# working.net
KiCad netlist of a schematic drawn in EAGLE
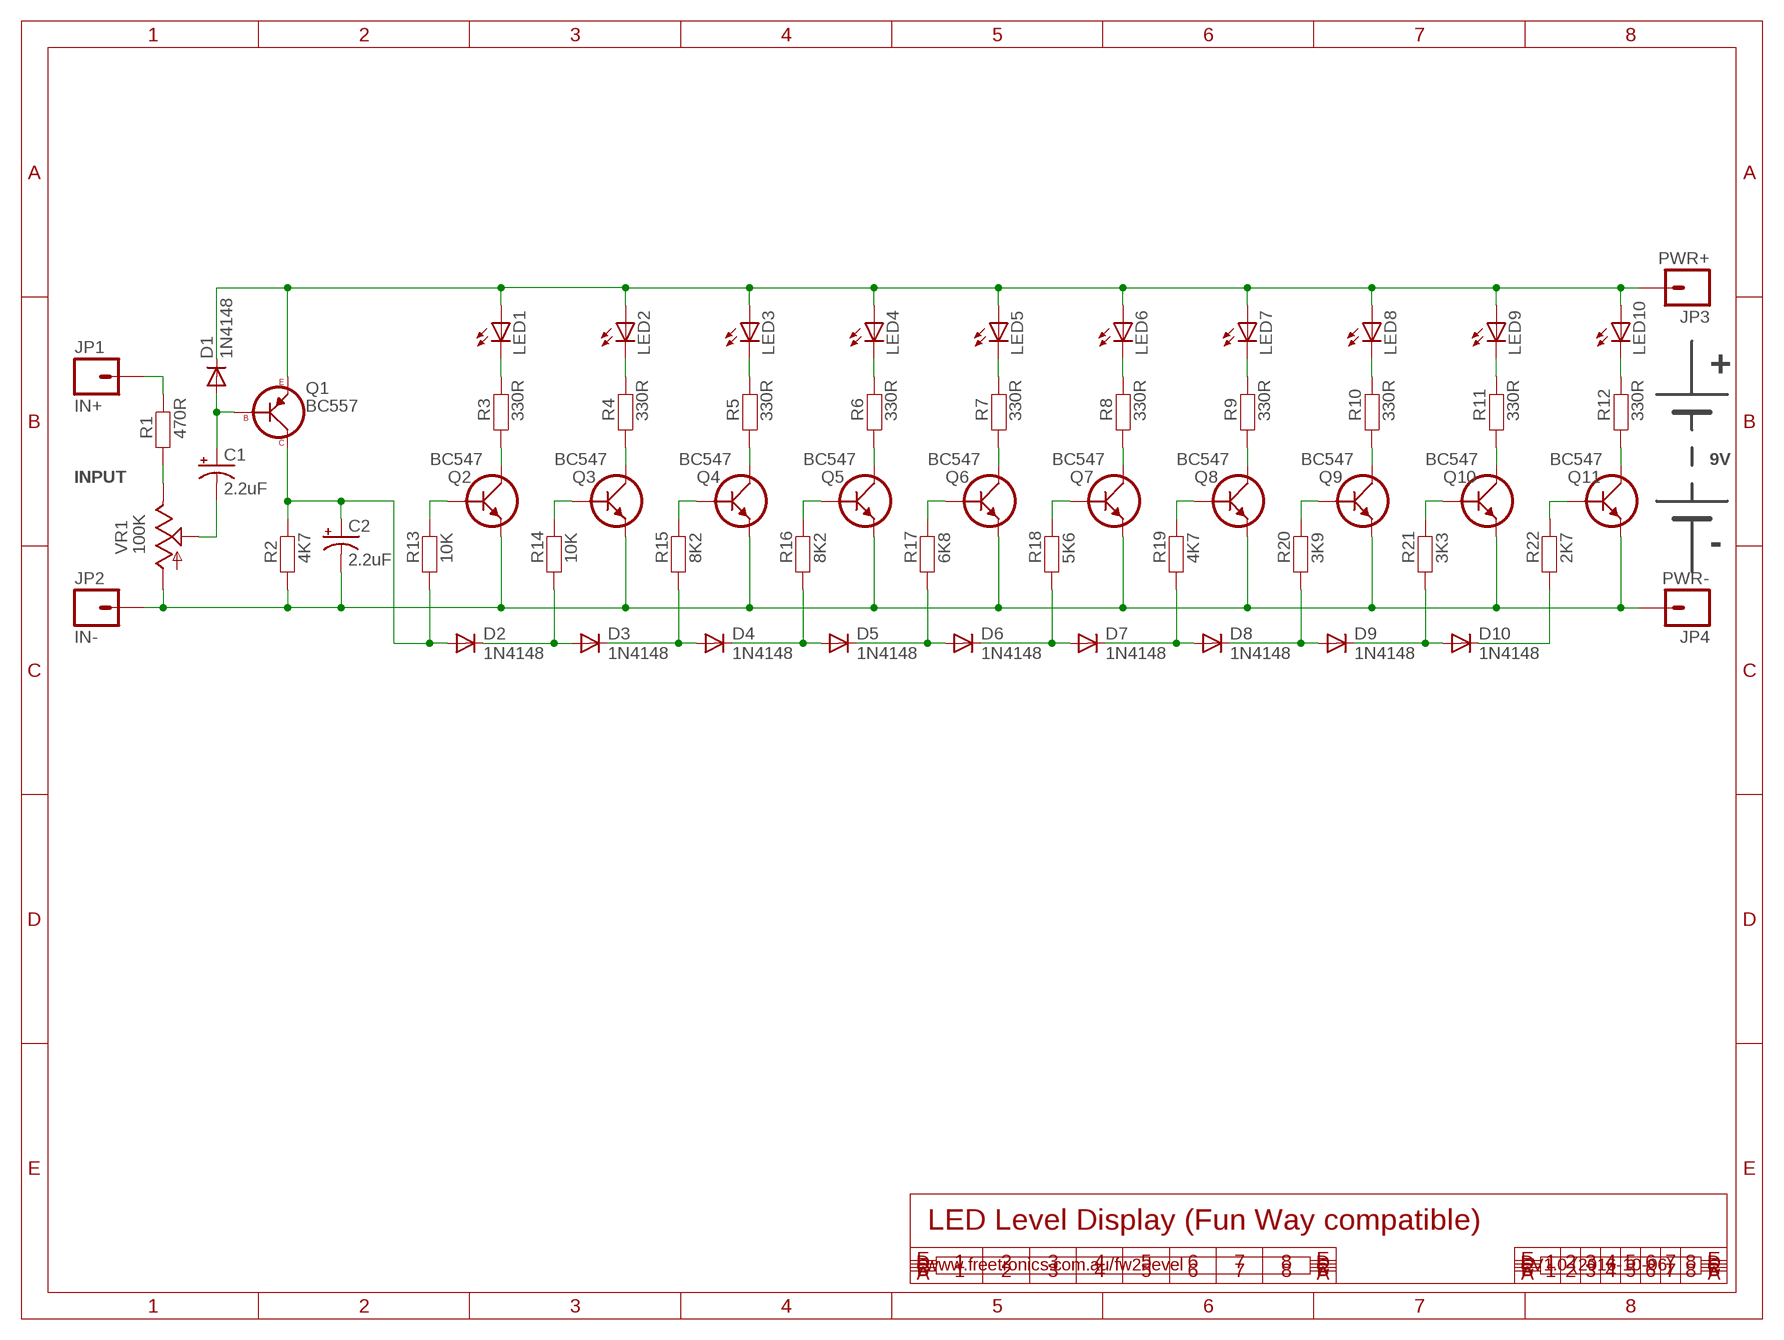
[diagram p0: schematic, sheet 1]

(export (version "E")
  (design (tool "Eeschema 10.0.6"))
  (components
    (comp (ref "C1")
      (value "2.2uF")
      (footprint "eagle-import:CPOL-RADIAL-100UF-25V")
      (libsource (lib "eagle-import") (part "CAP_POLPTH1"))
    )
    (comp (ref "C2")
      (value "2.2uF")
      (footprint "eagle-import:CPOL-RADIAL-100UF-25V")
      (libsource (lib "eagle-import") (part "CAP_POLPTH1"))
    )
    (comp (ref "D1")
      (value "1N4148")
      (footprint "eagle-import:DIODE-1N914L")
      (libsource (lib "eagle-import") (part "DIODE1N914L"))
    )
    (comp (ref "D2")
      (value "1N4148")
      (footprint "eagle-import:DIODE-1N914L")
      (libsource (lib "eagle-import") (part "DIODE1N914L"))
    )
    (comp (ref "D3")
      (value "1N4148")
      (footprint "eagle-import:DIODE-1N914L")
      (libsource (lib "eagle-import") (part "DIODE1N914L"))
    )
    (comp (ref "D4")
      (value "1N4148")
      (footprint "eagle-import:DIODE-1N914L")
      (libsource (lib "eagle-import") (part "DIODE1N914L"))
    )
    (comp (ref "D5")
      (value "1N4148")
      (footprint "eagle-import:DIODE-1N914L")
      (libsource (lib "eagle-import") (part "DIODE1N914L"))
    )
    (comp (ref "D6")
      (value "1N4148")
      (footprint "eagle-import:DIODE-1N914L")
      (libsource (lib "eagle-import") (part "DIODE1N914L"))
    )
    (comp (ref "D7")
      (value "1N4148")
      (footprint "eagle-import:DIODE-1N914L")
      (libsource (lib "eagle-import") (part "DIODE1N914L"))
    )
    (comp (ref "D8")
      (value "1N4148")
      (footprint "eagle-import:DIODE-1N914L")
      (libsource (lib "eagle-import") (part "DIODE1N914L"))
    )
    (comp (ref "D9")
      (value "1N4148")
      (footprint "eagle-import:DIODE-1N914L")
      (libsource (lib "eagle-import") (part "DIODE1N914L"))
    )
    (comp (ref "D10")
      (value "1N4148")
      (footprint "eagle-import:DIODE-1N914L")
      (libsource (lib "eagle-import") (part "DIODE1N914L"))
    )
    (comp (ref "JP1")
      (value "IN+")
      (footprint "eagle-import:1X01")
      (libsource (lib "eagle-import") (part "M01PTH"))
    )
    (comp (ref "JP2")
      (value "IN-")
      (footprint "eagle-import:1X01")
      (libsource (lib "eagle-import") (part "M01PTH"))
    )
    (comp (ref "JP3")
      (value "PWR+")
      (footprint "eagle-import:1X01")
      (libsource (lib "eagle-import") (part "M01PTH"))
    )
    (comp (ref "JP4")
      (value "PWR-")
      (footprint "eagle-import:1X01")
      (libsource (lib "eagle-import") (part "M01PTH"))
    )
    (comp (ref "LED1")
      (value "LED5MML")
      (footprint "eagle-import:LED5MMLARGE")
      (libsource (lib "eagle-import") (part "LED5MML"))
    )
    (comp (ref "LED2")
      (value "LED5MML")
      (footprint "eagle-import:LED5MMLARGE")
      (libsource (lib "eagle-import") (part "LED5MML"))
    )
    (comp (ref "LED3")
      (value "LED5MML")
      (footprint "eagle-import:LED5MMLARGE")
      (libsource (lib "eagle-import") (part "LED5MML"))
    )
    (comp (ref "LED4")
      (value "LED5MML")
      (footprint "eagle-import:LED5MMLARGE")
      (libsource (lib "eagle-import") (part "LED5MML"))
    )
    (comp (ref "LED5")
      (value "LED5MML")
      (footprint "eagle-import:LED5MMLARGE")
      (libsource (lib "eagle-import") (part "LED5MML"))
    )
    (comp (ref "LED6")
      (value "LED5MML")
      (footprint "eagle-import:LED5MMLARGE")
      (libsource (lib "eagle-import") (part "LED5MML"))
    )
    (comp (ref "LED7")
      (value "LED5MML")
      (footprint "eagle-import:LED5MMLARGE")
      (libsource (lib "eagle-import") (part "LED5MML"))
    )
    (comp (ref "LED8")
      (value "LED5MML")
      (footprint "eagle-import:LED5MMLARGE")
      (libsource (lib "eagle-import") (part "LED5MML"))
    )
    (comp (ref "LED9")
      (value "LED5MML")
      (footprint "eagle-import:LED5MMLARGE")
      (libsource (lib "eagle-import") (part "LED5MML"))
    )
    (comp (ref "LED10")
      (value "LED5MML")
      (footprint "eagle-import:LED5MMLARGE")
      (libsource (lib "eagle-import") (part "LED5MML"))
    )
    (comp (ref "Q1")
      (value "BC557")
      (footprint "eagle-import:TO-92")
      (libsource (lib "eagle-import") (part "BC557"))
    )
    (comp (ref "Q2")
      (value "BC547")
      (footprint "eagle-import:TO-92")
      (libsource (lib "eagle-import") (part "BC547"))
    )
    (comp (ref "Q3")
      (value "BC547")
      (footprint "eagle-import:TO-92")
      (libsource (lib "eagle-import") (part "BC547"))
    )
    (comp (ref "Q4")
      (value "BC547")
      (footprint "eagle-import:TO-92")
      (libsource (lib "eagle-import") (part "BC547"))
    )
    (comp (ref "Q5")
      (value "BC547")
      (footprint "eagle-import:TO-92")
      (libsource (lib "eagle-import") (part "BC547"))
    )
    (comp (ref "Q6")
      (value "BC547")
      (footprint "eagle-import:TO-92")
      (libsource (lib "eagle-import") (part "BC547"))
    )
    (comp (ref "Q7")
      (value "BC547")
      (footprint "eagle-import:TO-92")
      (libsource (lib "eagle-import") (part "BC547"))
    )
    (comp (ref "Q8")
      (value "BC547")
      (footprint "eagle-import:TO-92")
      (libsource (lib "eagle-import") (part "BC547"))
    )
    (comp (ref "Q9")
      (value "BC547")
      (footprint "eagle-import:TO-92")
      (libsource (lib "eagle-import") (part "BC547"))
    )
    (comp (ref "Q10")
      (value "BC547")
      (footprint "eagle-import:TO-92")
      (libsource (lib "eagle-import") (part "BC547"))
    )
    (comp (ref "Q11")
      (value "BC547")
      (footprint "eagle-import:TO-92")
      (libsource (lib "eagle-import") (part "BC547"))
    )
    (comp (ref "R1")
      (value "470R")
      (footprint "eagle-import:AXIAL-0.4-LARGE")
      (libsource (lib "eagle-import") (part "FREETRONICS_RESISTORPTH3"))
    )
    (comp (ref "R2")
      (value "4K7")
      (footprint "eagle-import:AXIAL-0.4-LARGE")
      (libsource (lib "eagle-import") (part "FREETRONICS_RESISTORPTH3"))
    )
    (comp (ref "R3")
      (value "330R")
      (footprint "eagle-import:0309VW")
      (libsource (lib "eagle-import") (part "RESISTORVERT3"))
    )
    (comp (ref "R4")
      (value "330R")
      (footprint "eagle-import:0309VW")
      (libsource (lib "eagle-import") (part "RESISTORVERT3"))
    )
    (comp (ref "R5")
      (value "330R")
      (footprint "eagle-import:0309VW")
      (libsource (lib "eagle-import") (part "RESISTORVERT3"))
    )
    (comp (ref "R6")
      (value "330R")
      (footprint "eagle-import:0309VW")
      (libsource (lib "eagle-import") (part "RESISTORVERT3"))
    )
    (comp (ref "R7")
      (value "330R")
      (footprint "eagle-import:0309VW")
      (libsource (lib "eagle-import") (part "RESISTORVERT3"))
    )
    (comp (ref "R8")
      (value "330R")
      (footprint "eagle-import:0309VW")
      (libsource (lib "eagle-import") (part "RESISTORVERT3"))
    )
    (comp (ref "R9")
      (value "330R")
      (footprint "eagle-import:0309VW")
      (libsource (lib "eagle-import") (part "RESISTORVERT3"))
    )
    (comp (ref "R10")
      (value "330R")
      (footprint "eagle-import:0309VW")
      (libsource (lib "eagle-import") (part "RESISTORVERT3"))
    )
    (comp (ref "R11")
      (value "330R")
      (footprint "eagle-import:0309VW")
      (libsource (lib "eagle-import") (part "RESISTORVERT3"))
    )
    (comp (ref "R12")
      (value "330R")
      (footprint "eagle-import:0309VW")
      (libsource (lib "eagle-import") (part "RESISTORVERT3"))
    )
    (comp (ref "R13")
      (value "10K")
      (footprint "eagle-import:0309VW")
      (libsource (lib "eagle-import") (part "RESISTORVERT3"))
    )
    (comp (ref "R14")
      (value "10K")
      (footprint "eagle-import:0309VW")
      (libsource (lib "eagle-import") (part "RESISTORVERT3"))
    )
    (comp (ref "R15")
      (value "8K2")
      (footprint "eagle-import:0309VW")
      (libsource (lib "eagle-import") (part "RESISTORVERT3"))
    )
    (comp (ref "R16")
      (value "8K2")
      (footprint "eagle-import:0309VW")
      (libsource (lib "eagle-import") (part "RESISTORVERT3"))
    )
    (comp (ref "R17")
      (value "6K8")
      (footprint "eagle-import:0309VW")
      (libsource (lib "eagle-import") (part "RESISTORVERT3"))
    )
    (comp (ref "R18")
      (value "5K6")
      (footprint "eagle-import:0309VW")
      (libsource (lib "eagle-import") (part "RESISTORVERT3"))
    )
    (comp (ref "R19")
      (value "4K7")
      (footprint "eagle-import:0309VW")
      (libsource (lib "eagle-import") (part "RESISTORVERT3"))
    )
    (comp (ref "R20")
      (value "3K9")
      (footprint "eagle-import:0309VW")
      (libsource (lib "eagle-import") (part "RESISTORVERT3"))
    )
    (comp (ref "R21")
      (value "3K3")
      (footprint "eagle-import:0309VW")
      (libsource (lib "eagle-import") (part "RESISTORVERT3"))
    )
    (comp (ref "R22")
      (value "2K7")
      (footprint "eagle-import:0309VW")
      (libsource (lib "eagle-import") (part "RESISTORVERT3"))
    )
    (comp (ref "VR1")
      (value "100K")
      (footprint "eagle-import:6MM")
      (libsource (lib "eagle-import") (part "TRIM"))
    )
  )
  (nets
    (net (code "1") (name "Net-(C1-+)") (class "Default")
      (node (ref "C1") (pin "1") (pinfunction "+_1") (pintype "passive"))
      (node (ref "D1") (pin "A") (pinfunction "A_A") (pintype "passive"))
      (node (ref "Q1") (pin "2") (pinfunction "B_2") (pintype "passive"))
    )
    (net (code "2") (name "Net-(C1--)") (class "Default")
      (node (ref "C1") (pin "2") (pinfunction "-_2") (pintype "passive"))
      (node (ref "VR1") (pin "S") (pinfunction "S_S") (pintype "passive"))
    )
    (net (code "3") (name "Net-(C2-+)") (class "Default")
      (node (ref "C2") (pin "1") (pinfunction "+_1") (pintype "passive"))
      (node (ref "D2") (pin "A") (pinfunction "A_A") (pintype "passive"))
      (node (ref "Q1") (pin "1") (pinfunction "C_1") (pintype "passive"))
      (node (ref "R13") (pin "1") (pinfunction "1_1") (pintype "passive"))
      (node (ref "R2") (pin "P$2") (pinfunction "2_P$2") (pintype "passive"))
    )
    (net (code "4") (name "Net-(C2--)") (class "Default")
      (node (ref "C2") (pin "2") (pinfunction "-_2") (pintype "passive"))
      (node (ref "JP2") (pin "1") (pinfunction "1_1") (pintype "passive"))
      (node (ref "JP4") (pin "1") (pinfunction "1_1") (pintype "passive"))
      (node (ref "Q10") (pin "3") (pinfunction "E_3") (pintype "passive"))
      (node (ref "Q11") (pin "3") (pinfunction "E_3") (pintype "passive"))
      (node (ref "Q2") (pin "3") (pinfunction "E_3") (pintype "passive"))
      (node (ref "Q3") (pin "3") (pinfunction "E_3") (pintype "passive"))
      (node (ref "Q4") (pin "3") (pinfunction "E_3") (pintype "passive"))
      (node (ref "Q5") (pin "3") (pinfunction "E_3") (pintype "passive"))
      (node (ref "Q6") (pin "3") (pinfunction "E_3") (pintype "passive"))
      (node (ref "Q7") (pin "3") (pinfunction "E_3") (pintype "passive"))
      (node (ref "Q8") (pin "3") (pinfunction "E_3") (pintype "passive"))
      (node (ref "Q9") (pin "3") (pinfunction "E_3") (pintype "passive"))
      (node (ref "R2") (pin "P$1") (pinfunction "1_P$1") (pintype "passive"))
      (node (ref "VR1") (pin "A") (pinfunction "A_A") (pintype "passive"))
    )
    (net (code "5") (name "Net-(D2-PadC)") (class "Default")
      (node (ref "D2") (pin "C") (pinfunction "C_C") (pintype "passive"))
      (node (ref "D3") (pin "A") (pinfunction "A_A") (pintype "passive"))
      (node (ref "R14") (pin "1") (pinfunction "1_1") (pintype "passive"))
    )
    (net (code "6") (name "Net-(D3-PadC)") (class "Default")
      (node (ref "D3") (pin "C") (pinfunction "C_C") (pintype "passive"))
      (node (ref "D4") (pin "A") (pinfunction "A_A") (pintype "passive"))
      (node (ref "R15") (pin "1") (pinfunction "1_1") (pintype "passive"))
    )
    (net (code "7") (name "Net-(D4-PadC)") (class "Default")
      (node (ref "D4") (pin "C") (pinfunction "C_C") (pintype "passive"))
      (node (ref "D5") (pin "A") (pinfunction "A_A") (pintype "passive"))
      (node (ref "R16") (pin "1") (pinfunction "1_1") (pintype "passive"))
    )
    (net (code "8") (name "Net-(D5-PadC)") (class "Default")
      (node (ref "D5") (pin "C") (pinfunction "C_C") (pintype "passive"))
      (node (ref "D6") (pin "A") (pinfunction "A_A") (pintype "passive"))
      (node (ref "R17") (pin "1") (pinfunction "1_1") (pintype "passive"))
    )
    (net (code "9") (name "Net-(D6-PadC)") (class "Default")
      (node (ref "D6") (pin "C") (pinfunction "C_C") (pintype "passive"))
      (node (ref "D7") (pin "A") (pinfunction "A_A") (pintype "passive"))
      (node (ref "R18") (pin "1") (pinfunction "1_1") (pintype "passive"))
    )
    (net (code "10") (name "Net-(D7-PadC)") (class "Default")
      (node (ref "D7") (pin "C") (pinfunction "C_C") (pintype "passive"))
      (node (ref "D8") (pin "A") (pinfunction "A_A") (pintype "passive"))
      (node (ref "R19") (pin "1") (pinfunction "1_1") (pintype "passive"))
    )
    (net (code "11") (name "Net-(D8-PadC)") (class "Default")
      (node (ref "D8") (pin "C") (pinfunction "C_C") (pintype "passive"))
      (node (ref "D9") (pin "A") (pinfunction "A_A") (pintype "passive"))
      (node (ref "R20") (pin "1") (pinfunction "1_1") (pintype "passive"))
    )
    (net (code "12") (name "Net-(D10-PadA)") (class "Default")
      (node (ref "D10") (pin "A") (pinfunction "A_A") (pintype "passive"))
      (node (ref "D9") (pin "C") (pinfunction "C_C") (pintype "passive"))
      (node (ref "R21") (pin "1") (pinfunction "1_1") (pintype "passive"))
    )
    (net (code "13") (name "Net-(D10-PadC)") (class "Default")
      (node (ref "D10") (pin "C") (pinfunction "C_C") (pintype "passive"))
      (node (ref "R22") (pin "1") (pinfunction "1_1") (pintype "passive"))
    )
    (net (code "14") (name "Net-(LED1-C)") (class "Default")
      (node (ref "LED1") (pin "K") (pinfunction "C_K") (pintype "passive"))
      (node (ref "R3") (pin "1") (pinfunction "1_1") (pintype "passive"))
    )
    (net (code "15") (name "Net-(LED2-C)") (class "Default")
      (node (ref "LED2") (pin "K") (pinfunction "C_K") (pintype "passive"))
      (node (ref "R4") (pin "1") (pinfunction "1_1") (pintype "passive"))
    )
    (net (code "16") (name "Net-(LED3-C)") (class "Default")
      (node (ref "LED3") (pin "K") (pinfunction "C_K") (pintype "passive"))
      (node (ref "R5") (pin "1") (pinfunction "1_1") (pintype "passive"))
    )
    (net (code "17") (name "Net-(LED4-C)") (class "Default")
      (node (ref "LED4") (pin "K") (pinfunction "C_K") (pintype "passive"))
      (node (ref "R6") (pin "1") (pinfunction "1_1") (pintype "passive"))
    )
    (net (code "18") (name "Net-(LED5-C)") (class "Default")
      (node (ref "LED5") (pin "K") (pinfunction "C_K") (pintype "passive"))
      (node (ref "R7") (pin "1") (pinfunction "1_1") (pintype "passive"))
    )
    (net (code "19") (name "Net-(LED6-C)") (class "Default")
      (node (ref "LED6") (pin "K") (pinfunction "C_K") (pintype "passive"))
      (node (ref "R8") (pin "1") (pinfunction "1_1") (pintype "passive"))
    )
    (net (code "20") (name "Net-(LED7-C)") (class "Default")
      (node (ref "LED7") (pin "K") (pinfunction "C_K") (pintype "passive"))
      (node (ref "R9") (pin "1") (pinfunction "1_1") (pintype "passive"))
    )
    (net (code "21") (name "Net-(LED8-C)") (class "Default")
      (node (ref "LED8") (pin "K") (pinfunction "C_K") (pintype "passive"))
      (node (ref "R10") (pin "1") (pinfunction "1_1") (pintype "passive"))
    )
    (net (code "22") (name "Net-(LED9-C)") (class "Default")
      (node (ref "LED9") (pin "K") (pinfunction "C_K") (pintype "passive"))
      (node (ref "R11") (pin "1") (pinfunction "1_1") (pintype "passive"))
    )
    (net (code "23") (name "Net-(LED10-C)") (class "Default")
      (node (ref "LED10") (pin "K") (pinfunction "C_K") (pintype "passive"))
      (node (ref "R12") (pin "1") (pinfunction "1_1") (pintype "passive"))
    )
    (net (code "24") (name "Net-(Q1-E)") (class "Default")
      (node (ref "D1") (pin "C") (pinfunction "C_C") (pintype "passive"))
      (node (ref "JP3") (pin "1") (pinfunction "1_1") (pintype "passive"))
      (node (ref "LED1") (pin "A") (pinfunction "A_A") (pintype "passive"))
      (node (ref "LED10") (pin "A") (pinfunction "A_A") (pintype "passive"))
      (node (ref "LED2") (pin "A") (pinfunction "A_A") (pintype "passive"))
      (node (ref "LED3") (pin "A") (pinfunction "A_A") (pintype "passive"))
      (node (ref "LED4") (pin "A") (pinfunction "A_A") (pintype "passive"))
      (node (ref "LED5") (pin "A") (pinfunction "A_A") (pintype "passive"))
      (node (ref "LED6") (pin "A") (pinfunction "A_A") (pintype "passive"))
      (node (ref "LED7") (pin "A") (pinfunction "A_A") (pintype "passive"))
      (node (ref "LED8") (pin "A") (pinfunction "A_A") (pintype "passive"))
      (node (ref "LED9") (pin "A") (pinfunction "A_A") (pintype "passive"))
      (node (ref "Q1") (pin "3") (pinfunction "E_3") (pintype "passive"))
    )
    (net (code "25") (name "Net-(Q2-B)") (class "Default")
      (node (ref "Q2") (pin "2") (pinfunction "B_2") (pintype "passive"))
      (node (ref "R13") (pin "2") (pinfunction "2_2") (pintype "passive"))
    )
    (net (code "26") (name "Net-(Q2-C)") (class "Default")
      (node (ref "Q2") (pin "1") (pinfunction "C_1") (pintype "passive"))
      (node (ref "R3") (pin "2") (pinfunction "2_2") (pintype "passive"))
    )
    (net (code "27") (name "Net-(Q3-B)") (class "Default")
      (node (ref "Q3") (pin "2") (pinfunction "B_2") (pintype "passive"))
      (node (ref "R14") (pin "2") (pinfunction "2_2") (pintype "passive"))
    )
    (net (code "28") (name "Net-(Q3-C)") (class "Default")
      (node (ref "Q3") (pin "1") (pinfunction "C_1") (pintype "passive"))
      (node (ref "R4") (pin "2") (pinfunction "2_2") (pintype "passive"))
    )
    (net (code "29") (name "Net-(Q4-B)") (class "Default")
      (node (ref "Q4") (pin "2") (pinfunction "B_2") (pintype "passive"))
      (node (ref "R15") (pin "2") (pinfunction "2_2") (pintype "passive"))
    )
    (net (code "30") (name "Net-(Q4-C)") (class "Default")
      (node (ref "Q4") (pin "1") (pinfunction "C_1") (pintype "passive"))
      (node (ref "R5") (pin "2") (pinfunction "2_2") (pintype "passive"))
    )
    (net (code "31") (name "Net-(Q5-B)") (class "Default")
      (node (ref "Q5") (pin "2") (pinfunction "B_2") (pintype "passive"))
      (node (ref "R16") (pin "2") (pinfunction "2_2") (pintype "passive"))
    )
    (net (code "32") (name "Net-(Q5-C)") (class "Default")
      (node (ref "Q5") (pin "1") (pinfunction "C_1") (pintype "passive"))
      (node (ref "R6") (pin "2") (pinfunction "2_2") (pintype "passive"))
    )
    (net (code "33") (name "Net-(Q6-B)") (class "Default")
      (node (ref "Q6") (pin "2") (pinfunction "B_2") (pintype "passive"))
      (node (ref "R17") (pin "2") (pinfunction "2_2") (pintype "passive"))
    )
    (net (code "34") (name "Net-(Q6-C)") (class "Default")
      (node (ref "Q6") (pin "1") (pinfunction "C_1") (pintype "passive"))
      (node (ref "R7") (pin "2") (pinfunction "2_2") (pintype "passive"))
    )
    (net (code "35") (name "Net-(Q7-B)") (class "Default")
      (node (ref "Q7") (pin "2") (pinfunction "B_2") (pintype "passive"))
      (node (ref "R18") (pin "2") (pinfunction "2_2") (pintype "passive"))
    )
    (net (code "36") (name "Net-(Q7-C)") (class "Default")
      (node (ref "Q7") (pin "1") (pinfunction "C_1") (pintype "passive"))
      (node (ref "R8") (pin "2") (pinfunction "2_2") (pintype "passive"))
    )
    (net (code "37") (name "Net-(Q8-B)") (class "Default")
      (node (ref "Q8") (pin "2") (pinfunction "B_2") (pintype "passive"))
      (node (ref "R19") (pin "2") (pinfunction "2_2") (pintype "passive"))
    )
    (net (code "38") (name "Net-(Q8-C)") (class "Default")
      (node (ref "Q8") (pin "1") (pinfunction "C_1") (pintype "passive"))
      (node (ref "R9") (pin "2") (pinfunction "2_2") (pintype "passive"))
    )
    (net (code "39") (name "Net-(Q9-B)") (class "Default")
      (node (ref "Q9") (pin "2") (pinfunction "B_2") (pintype "passive"))
      (node (ref "R20") (pin "2") (pinfunction "2_2") (pintype "passive"))
    )
    (net (code "40") (name "Net-(Q9-C)") (class "Default")
      (node (ref "Q9") (pin "1") (pinfunction "C_1") (pintype "passive"))
      (node (ref "R10") (pin "2") (pinfunction "2_2") (pintype "passive"))
    )
    (net (code "41") (name "Net-(Q10-B)") (class "Default")
      (node (ref "Q10") (pin "2") (pinfunction "B_2") (pintype "passive"))
      (node (ref "R21") (pin "2") (pinfunction "2_2") (pintype "passive"))
    )
    (net (code "42") (name "Net-(Q10-C)") (class "Default")
      (node (ref "Q10") (pin "1") (pinfunction "C_1") (pintype "passive"))
      (node (ref "R11") (pin "2") (pinfunction "2_2") (pintype "passive"))
    )
    (net (code "43") (name "Net-(Q11-B)") (class "Default")
      (node (ref "Q11") (pin "2") (pinfunction "B_2") (pintype "passive"))
      (node (ref "R22") (pin "2") (pinfunction "2_2") (pintype "passive"))
    )
    (net (code "44") (name "Net-(Q11-C)") (class "Default")
      (node (ref "Q11") (pin "1") (pinfunction "C_1") (pintype "passive"))
      (node (ref "R12") (pin "2") (pinfunction "2_2") (pintype "passive"))
    )
    (net (code "45") (name "Net-(R1-1)") (class "Default")
      (node (ref "R1") (pin "P$1") (pinfunction "1_P$1") (pintype "passive"))
      (node (ref "VR1") (pin "E") (pinfunction "E_E") (pintype "passive"))
    )
    (net (code "46") (name "Net-(R1-2)") (class "Default")
      (node (ref "JP1") (pin "1") (pinfunction "1_1") (pintype "passive"))
      (node (ref "R1") (pin "P$2") (pinfunction "2_P$2") (pintype "passive"))
    )
  )
)
